# eFuse.net
KiCad netlist of a schematic drawn in Altium Designer
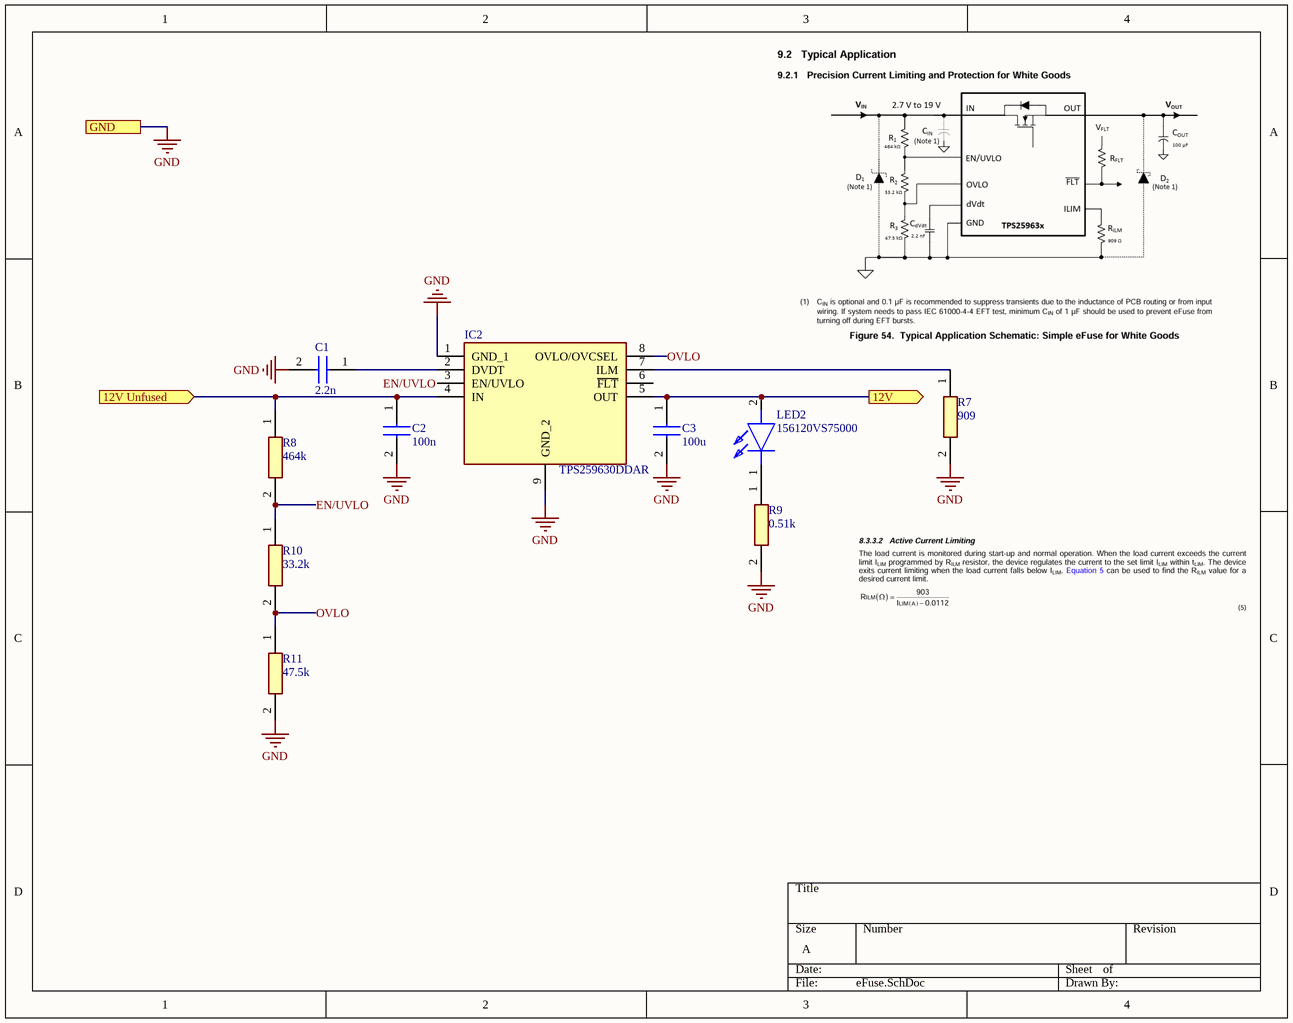
[diagram p0: eFuse.SchDoc]

(export (version "E")
  (design (tool "Eeschema 10.0.6"))
  (components
    (comp (ref "C1")
      (value "2.2n")
      (footprint "SamacSys:CAPC3216X94N")
      (description "Capacitor")
      (fields
        (field (name "MANUFACTURER_PART_NUMBER") "1206YC222KAT2A")
        (field (name "MOUSER PART NUMBER") "581-1206YC222KAT2A")
      )
      (libsource (lib "SamacSys") (part "1206YC222KAT2A"))
    )
    (comp (ref "C2")
      (value "100n")
      (footprint "SamacSys:CAPC3216X94N")
      (description "Capacitor")
      (fields
        (field (name "MANUFACTURER_PART_NUMBER") "12065C104J4Z2A")
        (field (name "MOUSER PART NUMBER") "581-12065C104J4Z2A")
      )
      (libsource (lib "SamacSys") (part "12065C104J4Z2A"))
    )
    (comp (ref "C3")
      (value "100u")
      (footprint "SamacSys:GRM31x")
      (description "Capacitor")
      (fields
        (field (name "MANUFACTURER_PART_NUMBER") "GRM31CR60J107KEA8L")
        (field (name "MOUSER PART NUMBER") "81-GRM31CR60J107KE8L")
      )
      (libsource (lib "SamacSys") (part "GRM31CR60J107KEA8L"))
    )
    (comp (ref "IC2")
      (value "TPS259630DDAR")
      (footprint "SamacSys:SOIC127P600X170-9N")
      (description "Integrated Circuit")
      (fields (field (name "MOUSER PART NUMBER") "595-TPS259630DDAR"))
      (libsource (lib "SamacSys") (part "TPS259630DDAR"))
    )
    (comp (ref "LED2")
      (value "156120VS75000")
      (footprint "SamacSys:156120VS75000")
      (description "LED")
      (fields (field (name "MOUSER PART NUMBER") "710-156120VS75000"))
      (libsource (lib "SamacSys") (part "156120VS75000"))
    )
    (comp (ref "R7")
      (value "909")
      (footprint "SamacSys:ERJ8ENF1000V")
      (description "Resistor")
      (fields
        (field (name "MANUFACTURER_PART_NUMBER") "ERJ-8ENF9090V")
        (field (name "MOUSER PART NUMBER") "667-ERJ-8ENF9090V")
      )
      (libsource (lib "SamacSys") (part "ERJ-8ENF9090V"))
    )
    (comp (ref "R8")
      (value "464k")
      (footprint "SamacSys:RESC3216X60N")
      (description "Resistor")
      (fields
        (field (name "MANUFACTURER_PART_NUMBER") "CRCW1206464KFKEA")
        (field (name "MOUSER PART NUMBER") "71-CRCW1206-464K-E3")
      )
      (libsource (lib "SamacSys") (part "CRCW1206464KFKEA"))
    )
    (comp (ref "R9")
      (value "0.51k")
      (footprint "SamacSys:RESC3216X65N")
      (description "Resistor")
      (fields
        (field (name "MANUFACTURER_PART_NUMBER") "KTR18EZPJ511")
        (field (name "MOUSER PART NUMBER") "755-KTR18EZPJ511")
      )
      (libsource (lib "SamacSys") (part "KTR18EZPJ511"))
    )
    (comp (ref "R10")
      (value "33.2k")
      (footprint "SamacSys:ERJ8ENF1000V")
      (description "Resistor")
      (fields
        (field (name "MANUFACTURER_PART_NUMBER") "ERJ-8ENF3322V")
        (field (name "MOUSER PART NUMBER") "667-ERJ-8ENF3322V")
      )
      (libsource (lib "SamacSys") (part "ERJ-8ENF3322V"))
    )
    (comp (ref "R11")
      (value "47.5k")
      (footprint "SamacSys:ERJ8ENF1000V")
      (description "Resistor")
      (fields
        (field (name "MANUFACTURER_PART_NUMBER") "ERJ-8ENF4752V")
        (field (name "MOUSER PART NUMBER") "667-ERJ-8ENF4752V")
      )
      (libsource (lib "SamacSys") (part "ERJ-8ENF4752V"))
    )
  )
  (nets
    (net (code "1") (name "/12V") (class "Default")
      (node (ref "C3") (pin "1") (pinfunction "1_1") (pintype "passive"))
      (node (ref "IC2") (pin "5") (pinfunction "OUT_5") (pintype "passive"))
      (node (ref "LED2") (pin "2") (pinfunction "A_2") (pintype "passive"))
    )
    (net (code "2") (name "/12V Unfused") (class "Default")
      (node (ref "C2") (pin "1") (pinfunction "1_1") (pintype "passive"))
      (node (ref "IC2") (pin "4") (pinfunction "IN_4") (pintype "passive"))
      (node (ref "R8") (pin "1") (pinfunction "1_1") (pintype "passive"))
    )
    (net (code "3") (name "/EN{slash}UVLO") (class "Default")
      (node (ref "IC2") (pin "3") (pinfunction "EN/UVLO_3") (pintype "passive"))
      (node (ref "R10") (pin "1") (pinfunction "1_1") (pintype "passive"))
      (node (ref "R8") (pin "2") (pinfunction "2_2") (pintype "passive"))
    )
    (net (code "4") (name "/OVLO") (class "Default")
      (node (ref "IC2") (pin "8") (pinfunction "OVLO/OVCSEL_8") (pintype "passive"))
      (node (ref "R10") (pin "2") (pinfunction "2_2") (pintype "passive"))
      (node (ref "R11") (pin "1") (pinfunction "1_1") (pintype "passive"))
    )
    (net (code "5") (name "GND") (class "Default")
      (node (ref "C1") (pin "2") (pinfunction "C2_2") (pintype "passive"))
      (node (ref "C2") (pin "2") (pinfunction "2_2") (pintype "passive"))
      (node (ref "C3") (pin "2") (pinfunction "2_2") (pintype "passive"))
      (node (ref "IC2") (pin "1") (pinfunction "GND_1_1") (pintype "passive"))
      (node (ref "IC2") (pin "9") (pinfunction "GND_2_9") (pintype "passive"))
      (node (ref "R11") (pin "2") (pinfunction "2_2") (pintype "passive"))
      (node (ref "R7") (pin "2") (pinfunction "2_2") (pintype "passive"))
      (node (ref "R9") (pin "2") (pinfunction "2_2") (pintype "passive"))
    )
    (net (code "6") (name "Net-(C1-C1)") (class "Default")
      (node (ref "C1") (pin "1") (pinfunction "C1_1") (pintype "passive"))
      (node (ref "IC2") (pin "2") (pinfunction "DVDT_2") (pintype "passive"))
    )
    (net (code "7") (name "Net-(IC2-ILM)") (class "Default")
      (node (ref "IC2") (pin "7") (pinfunction "ILM_7") (pintype "passive"))
      (node (ref "R7") (pin "1") (pinfunction "1_1") (pintype "passive"))
    )
    (net (code "8") (name "Net-(LED2-K)") (class "Default")
      (node (ref "LED2") (pin "1") (pinfunction "K_1") (pintype "passive"))
      (node (ref "R9") (pin "1") (pinfunction "1_1") (pintype "passive"))
    )
    (net (code "9") (name "unconnected-(IC2-~{FLT}-Pad6)") (class "Default")
      (node (ref "IC2") (pin "6") (pinfunction "~{FLT}_6") (pintype "passive"))
    )
  )
)
